# DHT11.net
KiCad netlist of a schematic drawn in Altium Designer
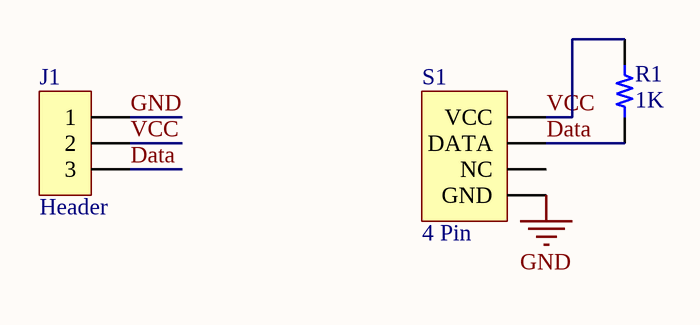
[diagram p0: DHT11.SchDoc]

(export (version "E")
  (design (tool "Eeschema 10.0.6"))
  (components
    (comp (ref "J1")
      (value "Header")
      (footprint "MOLEX SDA-70553-3PIN")
      (libsource (lib "Connectors") (part "3 Pin"))
    )
    (comp (ref "R1")
      (value "1K")
      (footprint "RES 1206/3216")
      (description "SMT Resistor")
      (libsource (lib "Cap_Res") (part "Resistor"))
    )
    (comp (ref "S1") (value "4 Pin") (footprint "DHT11") (libsource (lib "Sensors") (part "DHT11")))
  )
  (nets
    (net (code "1") (name "/Data") (class "Default")
      (node (ref "J1") (pin "3") (pinfunction "3_3") (pintype "passive"))
      (node (ref "R1") (pin "1") (pinfunction "1_1") (pintype "passive"))
      (node (ref "S1") (pin "2") (pinfunction "DATA_2") (pintype "passive"))
    )
    (net (code "2") (name "/VCC") (class "Default")
      (node (ref "J1") (pin "2") (pinfunction "2_2") (pintype "passive"))
      (node (ref "R1") (pin "2") (pinfunction "2_2") (pintype "passive"))
      (node (ref "S1") (pin "1") (pinfunction "VCC_1") (pintype "passive"))
    )
    (net (code "3") (name "GND") (class "Default")
      (node (ref "J1") (pin "1") (pinfunction "1_1") (pintype "passive"))
      (node (ref "S1") (pin "4") (pinfunction "GND_4") (pintype "passive"))
    )
    (net (code "4") (name "unconnected-(S1-NC-Pad3)") (class "Default")
      (node (ref "S1") (pin "3") (pinfunction "NC_3") (pintype "passive"))
    )
  )
)
